# max30105_breakout_iiT.net
KiCad netlist of a schematic drawn in EAGLE
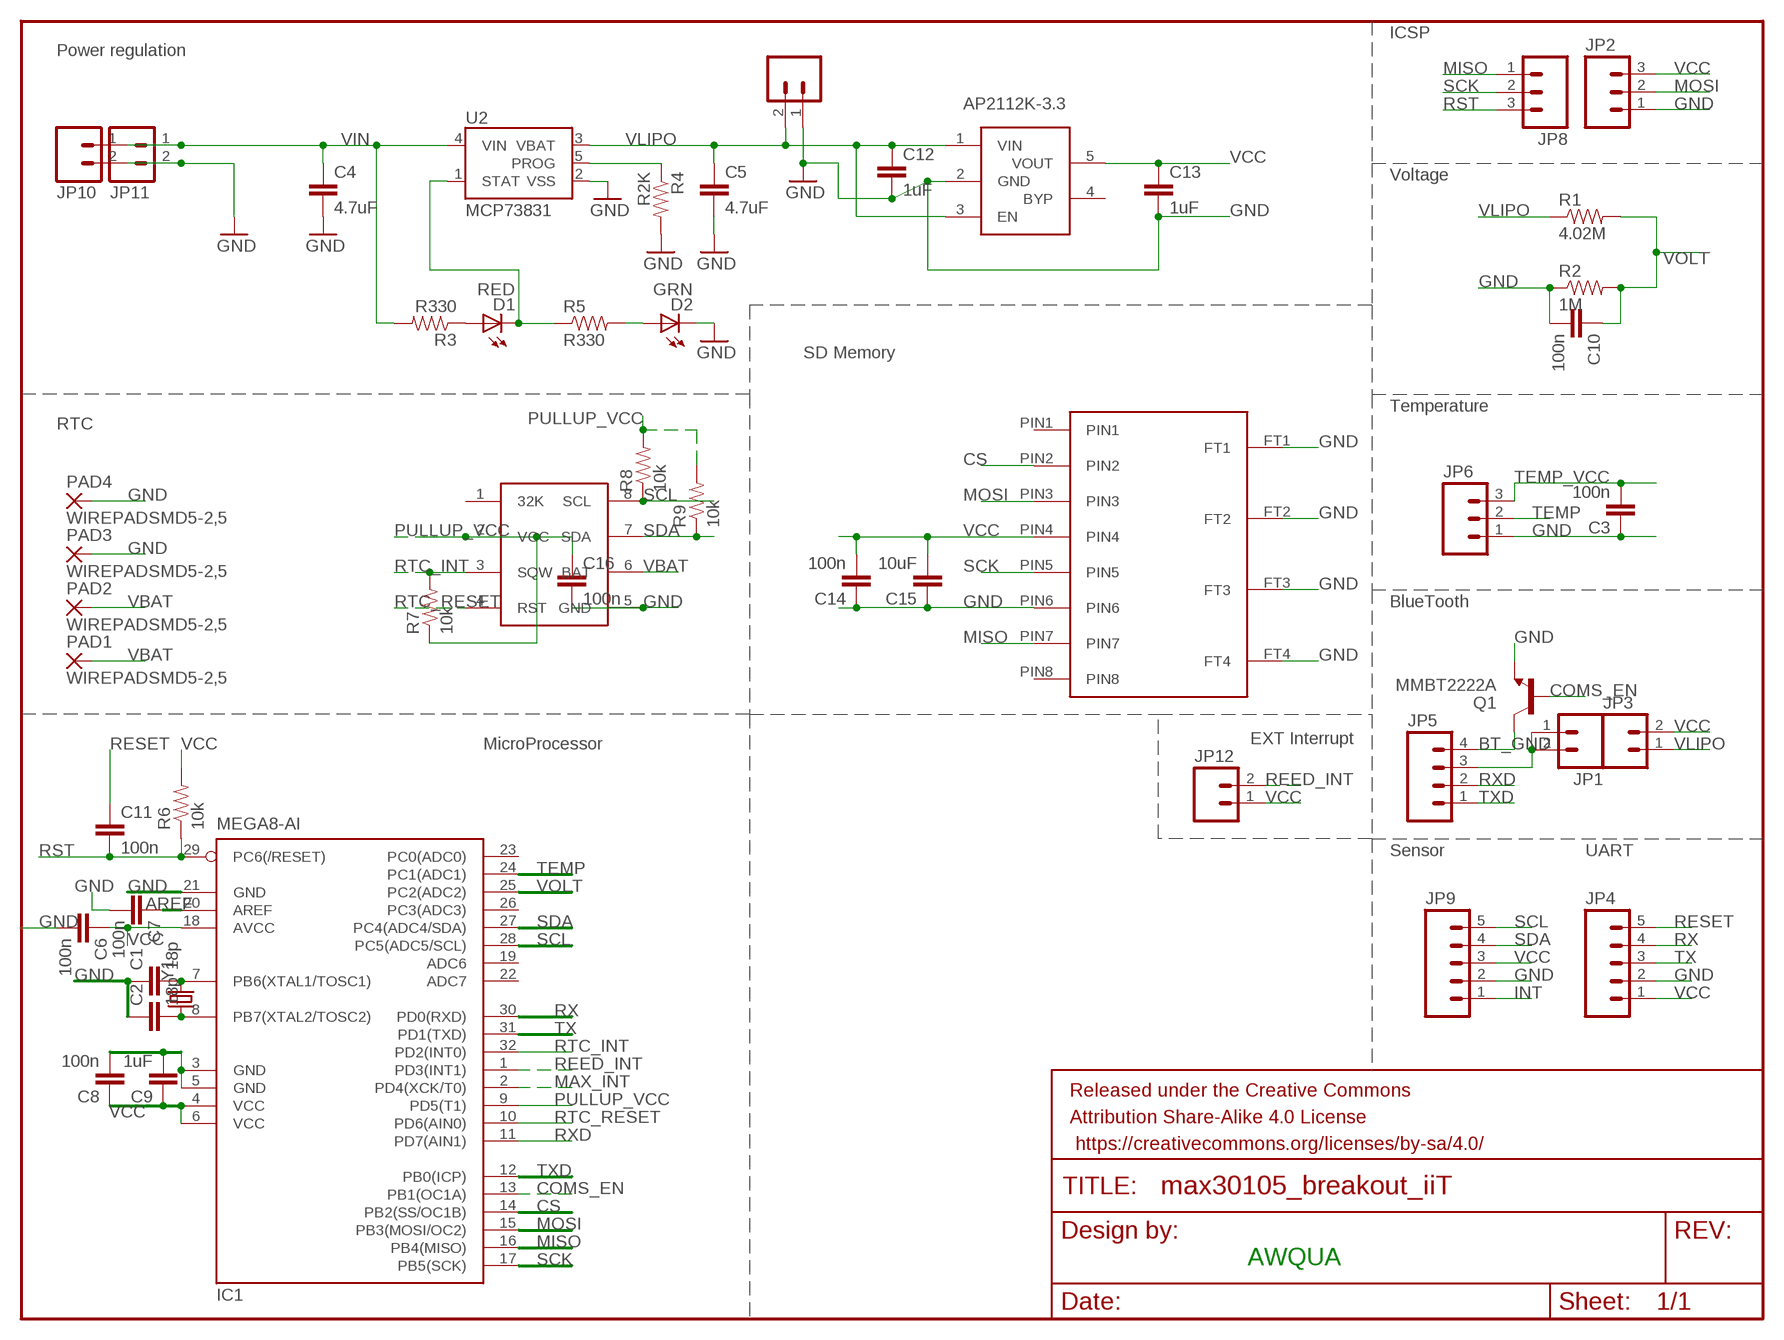
[diagram p0: schematic, sheet 1]

(export (version "E")
  (design (tool "Eeschema 10.0.6"))
  (components
    (comp (ref "*RTC")
      (value "DS3231M")
      (footprint "eagle-import:DS3231M")
      (libsource (lib "eagle-import") (part "DS3231M"))
    )
    (comp (ref "C1")
      (value "18p")
      (footprint "eagle-import:0603-CAP")
      (libsource (lib "eagle-import") (part "CAP0603-CAP"))
    )
    (comp (ref "C2")
      (value "18p")
      (footprint "eagle-import:0603-CAP")
      (libsource (lib "eagle-import") (part "CAP0603-CAP"))
    )
    (comp (ref "C3")
      (value "100n")
      (footprint "eagle-import:0603-CAP")
      (libsource (lib "eagle-import") (part "CAP0603-CAP"))
    )
    (comp (ref "C4")
      (value "4.7uF")
      (footprint "eagle-import:0603-CAP")
      (libsource (lib "eagle-import") (part "CAP0603-CAP"))
    )
    (comp (ref "C5")
      (value "4.7uF")
      (footprint "eagle-import:0603-CAP")
      (libsource (lib "eagle-import") (part "CAP0603-CAP"))
    )
    (comp (ref "C6")
      (value "100n")
      (footprint "eagle-import:0603-CAP")
      (libsource (lib "eagle-import") (part "CAP0603-CAP"))
    )
    (comp (ref "C7")
      (value "100n")
      (footprint "eagle-import:0603-CAP")
      (libsource (lib "eagle-import") (part "CAP0603-CAP"))
    )
    (comp (ref "C8")
      (value "100n")
      (footprint "eagle-import:0603-CAP")
      (libsource (lib "eagle-import") (part "CAP0603-CAP"))
    )
    (comp (ref "C9")
      (value "1uF")
      (footprint "eagle-import:0603-CAP")
      (libsource (lib "eagle-import") (part "CAP0603-CAP"))
    )
    (comp (ref "C10")
      (value "100n")
      (footprint "eagle-import:0603-CAP")
      (libsource (lib "eagle-import") (part "CAP0603-CAP"))
    )
    (comp (ref "C11")
      (value "100n")
      (footprint "eagle-import:0603-CAP")
      (libsource (lib "eagle-import") (part "CAP0603-CAP"))
    )
    (comp (ref "C12")
      (value "1uF")
      (footprint "eagle-import:0603-CAP")
      (libsource (lib "eagle-import") (part "CAP0603-CAP"))
    )
    (comp (ref "C13")
      (value "1uF")
      (footprint "eagle-import:0603-CAP")
      (libsource (lib "eagle-import") (part "CAP0603-CAP"))
    )
    (comp (ref "C14")
      (value "100n")
      (footprint "eagle-import:0603-CAP")
      (libsource (lib "eagle-import") (part "CAP0603-CAP"))
    )
    (comp (ref "C15")
      (value "10uF")
      (footprint "eagle-import:0603-CAP")
      (libsource (lib "eagle-import") (part "CAP0603-CAP"))
    )
    (comp (ref "C16")
      (value "100n")
      (footprint "eagle-import:0603-CAP")
      (libsource (lib "eagle-import") (part "CAP0603-CAP"))
    )
    (comp (ref "D1")
      (value "RED")
      (footprint "eagle-import:LED-0603")
      (libsource (lib "eagle-import") (part "LED0603"))
    )
    (comp (ref "D2")
      (value "GRN")
      (footprint "eagle-import:LED-0603")
      (libsource (lib "eagle-import") (part "LED0603"))
    )
    (comp (ref "FRAME1")
      (value "FRAME-LETTER")
      (footprint "eagle-import:CREATIVE_COMMONS")
      (libsource (lib "eagle-import") (part "FRAME-LETTER"))
    )
    (comp (ref "IC1")
      (value "MEGA8-AI")
      (footprint "eagle-import:TQFP32-08")
      (fields (field (name "MPN") "ATMEGA8-16AU"))
      (libsource (lib "eagle-import") (part "MEGA8-AI"))
    )
    (comp (ref "JP1")
      (value "M02PTH")
      (footprint "eagle-import:1X02")
      (libsource (lib "eagle-import") (part "SparkFun-Connectors_M02PTH"))
    )
    (comp (ref "JP2")
      (value "M03PTH")
      (footprint "eagle-import:1X03")
      (libsource (lib "eagle-import") (part "M03PTH"))
    )
    (comp (ref "JP3")
      (value "M02PTH")
      (footprint "eagle-import:1X02")
      (libsource (lib "eagle-import") (part "SparkFun-Connectors_M02PTH"))
    )
    (comp (ref "JP4")
      (value "M05PTH")
      (footprint "eagle-import:1X05")
      (libsource (lib "eagle-import") (part "M05PTH"))
    )
    (comp (ref "JP5")
      (value "M04PTH")
      (footprint "eagle-import:1X04")
      (libsource (lib "eagle-import") (part "M04PTH"))
    )
    (comp (ref "JP6")
      (value "M03PTH")
      (footprint "eagle-import:1X03")
      (libsource (lib "eagle-import") (part "M03PTH"))
    )
    (comp (ref "JP7")
      (value "LiPo Battery")
      (footprint "eagle-import:JST-2-SMD")
      (libsource (lib "eagle-import") (part "M02-JST-2MM-SMT"))
    )
    (comp (ref "JP8")
      (value "M03PTH")
      (footprint "eagle-import:1X03")
      (libsource (lib "eagle-import") (part "M03PTH"))
    )
    (comp (ref "JP9")
      (value "M05PTH")
      (footprint "eagle-import:1X05")
      (libsource (lib "eagle-import") (part "M05PTH"))
    )
    (comp (ref "JP10")
      (value "M02PTH")
      (footprint "eagle-import:1X02")
      (libsource (lib "eagle-import") (part "SparkFun-Connectors_M02PTH"))
    )
    (comp (ref "JP11")
      (value "M02PTH")
      (footprint "eagle-import:1X02")
      (libsource (lib "eagle-import") (part "SparkFun-Connectors_M02PTH"))
    )
    (comp (ref "JP12")
      (value "M02PTH")
      (footprint "eagle-import:1X02")
      (libsource (lib "eagle-import") (part "SparkFun-Connectors_M02PTH"))
    )
    (comp (ref "MICRO-SD")
      (value "MICROSD-1010030368")
      (footprint "eagle-import:MICROSD-1010030368")
      (libsource (lib "eagle-import") (part "MICROSD-1010030368"))
    )
    (comp (ref "PAD1")
      (value "WIREPADSMD5-2,5")
      (footprint "eagle-import:5-2,5")
      (libsource (lib "eagle-import") (part "WIREPADSMD5-2,5"))
    )
    (comp (ref "PAD2")
      (value "WIREPADSMD5-2,5")
      (footprint "eagle-import:5-2,5")
      (libsource (lib "eagle-import") (part "WIREPADSMD5-2,5"))
    )
    (comp (ref "PAD3")
      (value "WIREPADSMD5-2,5")
      (footprint "eagle-import:5-2,5")
      (libsource (lib "eagle-import") (part "WIREPADSMD5-2,5"))
    )
    (comp (ref "PAD4")
      (value "WIREPADSMD5-2,5")
      (footprint "eagle-import:5-2,5")
      (libsource (lib "eagle-import") (part "WIREPADSMD5-2,5"))
    )
    (comp (ref "Q1")
      (value "MMBT2222A")
      (footprint "eagle-import:SOT23-3")
      (libsource (lib "eagle-import") (part "TRANSISTOR_NPNMMBT2222A"))
    )
    (comp (ref "R1")
      (value "4.02M")
      (footprint "eagle-import:0603-RES")
      (libsource (lib "eagle-import") (part "RESISTOR0603"))
    )
    (comp (ref "R2")
      (value "1M")
      (footprint "eagle-import:0603-RES")
      (libsource (lib "eagle-import") (part "RESISTOR0603"))
    )
    (comp (ref "R3")
      (value "R330")
      (footprint "eagle-import:0603-RES")
      (libsource (lib "eagle-import") (part "RESISTOR0603-RES"))
    )
    (comp (ref "R4")
      (value "R2K")
      (footprint "eagle-import:0603-RES")
      (libsource (lib "eagle-import") (part "RESISTOR0603-RES"))
    )
    (comp (ref "R5")
      (value "R330")
      (footprint "eagle-import:0603-RES")
      (libsource (lib "eagle-import") (part "RESISTOR0603-RES"))
    )
    (comp (ref "R6")
      (value "10k")
      (footprint "eagle-import:0603-RES")
      (libsource (lib "eagle-import") (part "RESISTOR0603"))
    )
    (comp (ref "R7")
      (value "10k")
      (footprint "eagle-import:0603-RES")
      (libsource (lib "eagle-import") (part "RESISTOR0603"))
    )
    (comp (ref "R8")
      (value "10k")
      (footprint "eagle-import:0603-RES")
      (libsource (lib "eagle-import") (part "RESISTOR0603-RES"))
    )
    (comp (ref "R9")
      (value "10k")
      (footprint "eagle-import:0603-RES")
      (libsource (lib "eagle-import") (part "RESISTOR0603-RES"))
    )
    (comp (ref "U$6")
      (value "AP2112K-3.3")
      (footprint "eagle-import:LP2985")
      (libsource (lib "eagle-import") (part "LP2985"))
    )
    (comp (ref "U2")
      (value "MCP73831")
      (footprint "eagle-import:SOT23-5")
      (libsource (lib "eagle-import") (part "MCP73831"))
    )
    (comp (ref "Y1")
      (value "CRYSTAL5X3")
      (footprint "eagle-import:CRYSTAL-SMD-5X3")
      (libsource (lib "eagle-import") (part "CRYSTAL5X3"))
    )
  )
  (nets
    (net (code "1") (name "/AREF") (class "Default")
      (node (ref "C7") (pin "1") (pinfunction "1_1") (pintype "passive"))
      (node (ref "IC1") (pin "20") (pinfunction "AREF_20") (pintype "passive"))
    )
    (net (code "2") (name "/BT_GND") (class "Default")
      (node (ref "JP5") (pin "4") (pinfunction "4_4") (pintype "passive"))
      (node (ref "Q1") (pin "3") (pinfunction "C_3") (pintype "passive"))
    )
    (net (code "3") (name "/COMS_EN") (class "Default")
      (node (ref "IC1") (pin "13") (pinfunction "PB1(OC1A)_13") (pintype "bidirectional"))
      (node (ref "Q1") (pin "1") (pinfunction "B_1") (pintype "passive"))
    )
    (net (code "4") (name "/CS") (class "Default")
      (node (ref "IC1") (pin "14") (pinfunction "PB2(SS/OC1B)_14") (pintype "bidirectional"))
      (node (ref "MICRO-SD") (pin "PIN2") (pinfunction "PIN2_PIN2") (pintype "bidirectional"))
    )
    (net (code "5") (name "/INT") (class "Default")
      (node (ref "JP9") (pin "1") (pinfunction "1_1") (pintype "passive"))
    )
    (net (code "6") (name "/MAX_INT") (class "Default")
      (node (ref "IC1") (pin "2") (pinfunction "PD4(XCK/T0)_2") (pintype "bidirectional"))
    )
    (net (code "7") (name "/MISO") (class "Default")
      (node (ref "IC1") (pin "16") (pinfunction "PB4(MISO)_16") (pintype "bidirectional"))
      (node (ref "JP8") (pin "1") (pinfunction "1_1") (pintype "passive"))
      (node (ref "MICRO-SD") (pin "PIN7") (pinfunction "PIN7_PIN7") (pintype "bidirectional"))
    )
    (net (code "8") (name "/MOSI") (class "Default")
      (node (ref "IC1") (pin "15") (pinfunction "PB3(MOSI/OC2)_15") (pintype "bidirectional"))
      (node (ref "JP2") (pin "2") (pinfunction "2_2") (pintype "passive"))
      (node (ref "MICRO-SD") (pin "PIN3") (pinfunction "PIN3_PIN3") (pintype "bidirectional"))
    )
    (net (code "9") (name "/PULLUP_VCC") (class "Default")
      (node (ref "*RTC") (pin "2") (pinfunction "VCC_2") (pintype "bidirectional"))
      (node (ref "C16") (pin "1") (pinfunction "1_1") (pintype "passive"))
      (node (ref "IC1") (pin "9") (pinfunction "PD5(T1)_9") (pintype "bidirectional"))
      (node (ref "R7") (pin "1") (pinfunction "1_1") (pintype "passive"))
      (node (ref "R8") (pin "2") (pinfunction "2_2") (pintype "passive"))
      (node (ref "R9") (pin "2") (pinfunction "2_2") (pintype "passive"))
    )
    (net (code "10") (name "/REED_INT") (class "Default")
      (node (ref "IC1") (pin "1") (pinfunction "PD3(INT1)_1") (pintype "bidirectional"))
      (node (ref "JP12") (pin "2") (pinfunction "2_2") (pintype "passive"))
    )
    (net (code "11") (name "/RESET") (class "Default")
      (node (ref "C11") (pin "1") (pinfunction "1_1") (pintype "passive"))
      (node (ref "JP4") (pin "5") (pinfunction "5_5") (pintype "passive"))
    )
    (net (code "12") (name "/RST") (class "Default")
      (node (ref "C11") (pin "2") (pinfunction "2_2") (pintype "passive"))
      (node (ref "IC1") (pin "29") (pinfunction "PC6(/RESET)_29") (pintype "bidirectional"))
      (node (ref "JP8") (pin "3") (pinfunction "3_3") (pintype "passive"))
      (node (ref "R6") (pin "1") (pinfunction "1_1") (pintype "passive"))
    )
    (net (code "13") (name "/RTC_INT") (class "Default")
      (node (ref "*RTC") (pin "3") (pinfunction "SQW_3") (pintype "bidirectional"))
      (node (ref "IC1") (pin "32") (pinfunction "PD2(INT0)_32") (pintype "bidirectional"))
      (node (ref "R7") (pin "2") (pinfunction "2_2") (pintype "passive"))
    )
    (net (code "14") (name "/RTC_RESET") (class "Default")
      (node (ref "*RTC") (pin "4") (pinfunction "RST_4") (pintype "bidirectional"))
      (node (ref "IC1") (pin "10") (pinfunction "PD6(AIN0)_10") (pintype "bidirectional"))
    )
    (net (code "15") (name "/RX") (class "Default")
      (node (ref "IC1") (pin "30") (pinfunction "PD0(RXD)_30") (pintype "bidirectional"))
      (node (ref "JP4") (pin "4") (pinfunction "4_4") (pintype "passive"))
    )
    (net (code "16") (name "/RXD") (class "Default")
      (node (ref "IC1") (pin "11") (pinfunction "PD7(AIN1)_11") (pintype "bidirectional"))
      (node (ref "JP5") (pin "2") (pinfunction "2_2") (pintype "passive"))
    )
    (net (code "17") (name "/SCK") (class "Default")
      (node (ref "IC1") (pin "17") (pinfunction "PB5(SCK)_17") (pintype "bidirectional"))
      (node (ref "JP8") (pin "2") (pinfunction "2_2") (pintype "passive"))
      (node (ref "MICRO-SD") (pin "PIN5") (pinfunction "PIN5_PIN5") (pintype "bidirectional"))
    )
    (net (code "18") (name "/SCL") (class "Default")
      (node (ref "*RTC") (pin "8") (pinfunction "SCL_8") (pintype "bidirectional"))
      (node (ref "IC1") (pin "28") (pinfunction "PC5(ADC5/SCL)_28") (pintype "bidirectional"))
      (node (ref "JP9") (pin "5") (pinfunction "5_5") (pintype "passive"))
      (node (ref "R8") (pin "1") (pinfunction "1_1") (pintype "passive"))
    )
    (net (code "19") (name "/SDA") (class "Default")
      (node (ref "*RTC") (pin "7") (pinfunction "SDA_7") (pintype "bidirectional"))
      (node (ref "IC1") (pin "27") (pinfunction "PC4(ADC4/SDA)_27") (pintype "bidirectional"))
      (node (ref "JP9") (pin "4") (pinfunction "4_4") (pintype "passive"))
      (node (ref "R9") (pin "1") (pinfunction "1_1") (pintype "passive"))
    )
    (net (code "20") (name "/TEMP") (class "Default")
      (node (ref "IC1") (pin "24") (pinfunction "PC1(ADC1)_24") (pintype "bidirectional"))
      (node (ref "JP6") (pin "2") (pinfunction "2_2") (pintype "passive"))
    )
    (net (code "21") (name "/TEMP_VCC") (class "Default")
      (node (ref "C3") (pin "2") (pinfunction "2_2") (pintype "passive"))
      (node (ref "JP6") (pin "3") (pinfunction "3_3") (pintype "passive"))
    )
    (net (code "22") (name "/TX") (class "Default")
      (node (ref "IC1") (pin "31") (pinfunction "PD1(TXD)_31") (pintype "bidirectional"))
      (node (ref "JP4") (pin "3") (pinfunction "3_3") (pintype "passive"))
    )
    (net (code "23") (name "/TXD") (class "Default")
      (node (ref "IC1") (pin "12") (pinfunction "PB0(ICP)_12") (pintype "bidirectional"))
      (node (ref "JP5") (pin "1") (pinfunction "1_1") (pintype "passive"))
    )
    (net (code "24") (name "/VBAT") (class "Default")
      (node (ref "*RTC") (pin "6") (pinfunction "BAT_6") (pintype "bidirectional"))
      (node (ref "PAD1") (pin "1") (pinfunction "P_1") (pintype "passive"))
      (node (ref "PAD2") (pin "1") (pinfunction "P_1") (pintype "passive"))
    )
    (net (code "25") (name "/VCC") (class "Default")
      (node (ref "C13") (pin "1") (pinfunction "1_1") (pintype "passive"))
      (node (ref "C14") (pin "2") (pinfunction "2_2") (pintype "passive"))
      (node (ref "C15") (pin "2") (pinfunction "2_2") (pintype "passive"))
      (node (ref "C6") (pin "1") (pinfunction "1_1") (pintype "passive"))
      (node (ref "C8") (pin "1") (pinfunction "1_1") (pintype "passive"))
      (node (ref "C9") (pin "1") (pinfunction "1_1") (pintype "passive"))
      (node (ref "IC1") (pin "18") (pinfunction "AVCC_18") (pintype "power_in"))
      (node (ref "IC1") (pin "4") (pinfunction "VCC_4") (pintype "power_in"))
      (node (ref "IC1") (pin "6") (pinfunction "VCC_6") (pintype "power_in"))
      (node (ref "JP12") (pin "1") (pinfunction "1_1") (pintype "passive"))
      (node (ref "JP2") (pin "3") (pinfunction "3_3") (pintype "passive"))
      (node (ref "JP3") (pin "2") (pinfunction "2_2") (pintype "passive"))
      (node (ref "JP4") (pin "1") (pinfunction "1_1") (pintype "passive"))
      (node (ref "JP9") (pin "3") (pinfunction "3_3") (pintype "passive"))
      (node (ref "MICRO-SD") (pin "PIN4") (pinfunction "PIN4_PIN4") (pintype "bidirectional"))
      (node (ref "R6") (pin "2") (pinfunction "2_2") (pintype "passive"))
      (node (ref "U$6") (pin "5") (pinfunction "VOUT_5") (pintype "bidirectional"))
    )
    (net (code "26") (name "/VIN") (class "Default")
      (node (ref "C4") (pin "1") (pinfunction "1_1") (pintype "passive"))
      (node (ref "JP10") (pin "1") (pinfunction "1_1") (pintype "passive"))
      (node (ref "JP11") (pin "1") (pinfunction "1_1") (pintype "passive"))
      (node (ref "R3") (pin "2") (pinfunction "2_2") (pintype "passive"))
      (node (ref "U2") (pin "4") (pinfunction "VIN_4") (pintype "power_in"))
    )
    (net (code "27") (name "/VLIPO") (class "Default")
      (node (ref "C12") (pin "1") (pinfunction "1_1") (pintype "passive"))
      (node (ref "C5") (pin "1") (pinfunction "1_1") (pintype "passive"))
      (node (ref "JP3") (pin "1") (pinfunction "1_1") (pintype "passive"))
      (node (ref "JP7") (pin "2") (pinfunction "2_2") (pintype "passive"))
      (node (ref "R1") (pin "1") (pinfunction "1_1") (pintype "passive"))
      (node (ref "U$6") (pin "1") (pinfunction "VIN_1") (pintype "bidirectional"))
      (node (ref "U$6") (pin "3") (pinfunction "EN_3") (pintype "bidirectional"))
      (node (ref "U2") (pin "3") (pinfunction "VBAT_3") (pintype "power_in"))
    )
    (net (code "28") (name "/VOLT") (class "Default")
      (node (ref "C10") (pin "1") (pinfunction "1_1") (pintype "passive"))
      (node (ref "IC1") (pin "25") (pinfunction "PC2(ADC2)_25") (pintype "bidirectional"))
      (node (ref "R1") (pin "2") (pinfunction "2_2") (pintype "passive"))
      (node (ref "R2") (pin "2") (pinfunction "2_2") (pintype "passive"))
    )
    (net (code "29") (name "GND") (class "Default")
      (node (ref "*RTC") (pin "5") (pinfunction "GND_5") (pintype "bidirectional"))
      (node (ref "C1") (pin "1") (pinfunction "1_1") (pintype "passive"))
      (node (ref "C10") (pin "2") (pinfunction "2_2") (pintype "passive"))
      (node (ref "C12") (pin "2") (pinfunction "2_2") (pintype "passive"))
      (node (ref "C13") (pin "2") (pinfunction "2_2") (pintype "passive"))
      (node (ref "C14") (pin "1") (pinfunction "1_1") (pintype "passive"))
      (node (ref "C15") (pin "1") (pinfunction "1_1") (pintype "passive"))
      (node (ref "C16") (pin "2") (pinfunction "2_2") (pintype "passive"))
      (node (ref "C2") (pin "1") (pinfunction "1_1") (pintype "passive"))
      (node (ref "C3") (pin "1") (pinfunction "1_1") (pintype "passive"))
      (node (ref "C4") (pin "2") (pinfunction "2_2") (pintype "passive"))
      (node (ref "C5") (pin "2") (pinfunction "2_2") (pintype "passive"))
      (node (ref "C6") (pin "2") (pinfunction "2_2") (pintype "passive"))
      (node (ref "C7") (pin "2") (pinfunction "2_2") (pintype "passive"))
      (node (ref "C8") (pin "2") (pinfunction "2_2") (pintype "passive"))
      (node (ref "C9") (pin "2") (pinfunction "2_2") (pintype "passive"))
      (node (ref "D2") (pin "C") (pinfunction "C_C") (pintype "passive"))
      (node (ref "IC1") (pin "21") (pinfunction "GND_21") (pintype "power_in"))
      (node (ref "IC1") (pin "3") (pinfunction "GND_3") (pintype "power_in"))
      (node (ref "IC1") (pin "5") (pinfunction "GND_5") (pintype "power_in"))
      (node (ref "JP10") (pin "2") (pinfunction "2_2") (pintype "passive"))
      (node (ref "JP11") (pin "2") (pinfunction "2_2") (pintype "passive"))
      (node (ref "JP2") (pin "1") (pinfunction "1_1") (pintype "passive"))
      (node (ref "JP4") (pin "2") (pinfunction "2_2") (pintype "passive"))
      (node (ref "JP6") (pin "1") (pinfunction "1_1") (pintype "passive"))
      (node (ref "JP7") (pin "1") (pinfunction "1_1") (pintype "passive"))
      (node (ref "JP9") (pin "2") (pinfunction "2_2") (pintype "passive"))
      (node (ref "MICRO-SD") (pin "FT1") (pinfunction "FT1_FT1") (pintype "bidirectional"))
      (node (ref "MICRO-SD") (pin "FT2") (pinfunction "FT2_FT2") (pintype "bidirectional"))
      (node (ref "MICRO-SD") (pin "FT3") (pinfunction "FT3_FT3") (pintype "bidirectional"))
      (node (ref "MICRO-SD") (pin "FT4") (pinfunction "FT4_FT4") (pintype "bidirectional"))
      (node (ref "MICRO-SD") (pin "PIN6") (pinfunction "PIN6_PIN6") (pintype "bidirectional"))
      (node (ref "PAD3") (pin "1") (pinfunction "P_1") (pintype "passive"))
      (node (ref "PAD4") (pin "1") (pinfunction "P_1") (pintype "passive"))
      (node (ref "Q1") (pin "2") (pinfunction "E_2") (pintype "passive"))
      (node (ref "R2") (pin "1") (pinfunction "1_1") (pintype "passive"))
      (node (ref "R4") (pin "2") (pinfunction "2_2") (pintype "passive"))
      (node (ref "U$6") (pin "2") (pinfunction "GND_2") (pintype "bidirectional"))
      (node (ref "U2") (pin "2") (pinfunction "VSS_2") (pintype "power_in"))
    )
    (net (code "30") (name "Net-(D1-PadA)") (class "Default")
      (node (ref "D1") (pin "A") (pinfunction "A_A") (pintype "passive"))
      (node (ref "R3") (pin "1") (pinfunction "1_1") (pintype "passive"))
    )
    (net (code "31") (name "Net-(D2-PadA)") (class "Default")
      (node (ref "D2") (pin "A") (pinfunction "A_A") (pintype "passive"))
      (node (ref "R5") (pin "2") (pinfunction "2_2") (pintype "passive"))
    )
    (net (code "32") (name "Net-(IC1-PB6(XTAL1{slash}TOSC1))") (class "Default")
      (node (ref "C1") (pin "2") (pinfunction "2_2") (pintype "passive"))
      (node (ref "IC1") (pin "7") (pinfunction "PB6(XTAL1/TOSC1)_7") (pintype "bidirectional"))
      (node (ref "Y1") (pin "3") (pinfunction "2_3") (pintype "passive"))
    )
    (net (code "33") (name "Net-(IC1-PB7(XTAL2{slash}TOSC2))") (class "Default")
      (node (ref "C2") (pin "2") (pinfunction "2_2") (pintype "passive"))
      (node (ref "IC1") (pin "8") (pinfunction "PB7(XTAL2/TOSC2)_8") (pintype "bidirectional"))
      (node (ref "Y1") (pin "1") (pinfunction "1_1") (pintype "passive"))
    )
    (net (code "34") (name "Net-(JP1-Pad1)") (class "Default")
      (node (ref "JP1") (pin "1") (pinfunction "1_1") (pintype "passive"))
      (node (ref "JP1") (pin "2") (pinfunction "2_2") (pintype "passive"))
      (node (ref "JP5") (pin "3") (pinfunction "3_3") (pintype "passive"))
    )
    (net (code "35") (name "Net-(U2-PROG)") (class "Default")
      (node (ref "R4") (pin "1") (pinfunction "1_1") (pintype "passive"))
      (node (ref "U2") (pin "5") (pinfunction "PROG_5") (pintype "input"))
    )
    (net (code "36") (name "Net-(U2-STAT)") (class "Default")
      (node (ref "D1") (pin "C") (pinfunction "C_C") (pintype "passive"))
      (node (ref "R5") (pin "1") (pinfunction "1_1") (pintype "passive"))
      (node (ref "U2") (pin "1") (pinfunction "STAT_1") (pintype "output"))
    )
    (net (code "37") (name "unconnected-(*RTC-32K-Pad1)") (class "Default")
      (node (ref "*RTC") (pin "1") (pinfunction "32K_1") (pintype "bidirectional"))
    )
    (net (code "38") (name "unconnected-(IC1-ADC6-Pad19)") (class "Default")
      (node (ref "IC1") (pin "19") (pinfunction "ADC6_19") (pintype "bidirectional"))
    )
    (net (code "39") (name "unconnected-(IC1-ADC7-Pad22)") (class "Default")
      (node (ref "IC1") (pin "22") (pinfunction "ADC7_22") (pintype "bidirectional"))
    )
    (net (code "40") (name "unconnected-(IC1-PC0(ADC0)-Pad23)") (class "Default")
      (node (ref "IC1") (pin "23") (pinfunction "PC0(ADC0)_23") (pintype "bidirectional"))
    )
    (net (code "41") (name "unconnected-(IC1-PC3(ADC3)-Pad26)") (class "Default")
      (node (ref "IC1") (pin "26") (pinfunction "PC3(ADC3)_26") (pintype "bidirectional"))
    )
    (net (code "42") (name "unconnected-(MICRO-SD-PadPIN1)") (class "Default")
      (node (ref "MICRO-SD") (pin "PIN1") (pinfunction "PIN1_PIN1") (pintype "bidirectional"))
    )
    (net (code "43") (name "unconnected-(MICRO-SD-PadPIN8)") (class "Default")
      (node (ref "MICRO-SD") (pin "PIN8") (pinfunction "PIN8_PIN8") (pintype "bidirectional"))
    )
    (net (code "44") (name "unconnected-(U$6-BYP-Pad4)") (class "Default")
      (node (ref "U$6") (pin "4") (pinfunction "BYP_4") (pintype "bidirectional"))
    )
  )
)
